# e-wall-smd.net
KiCad netlist of a schematic drawn in EAGLE
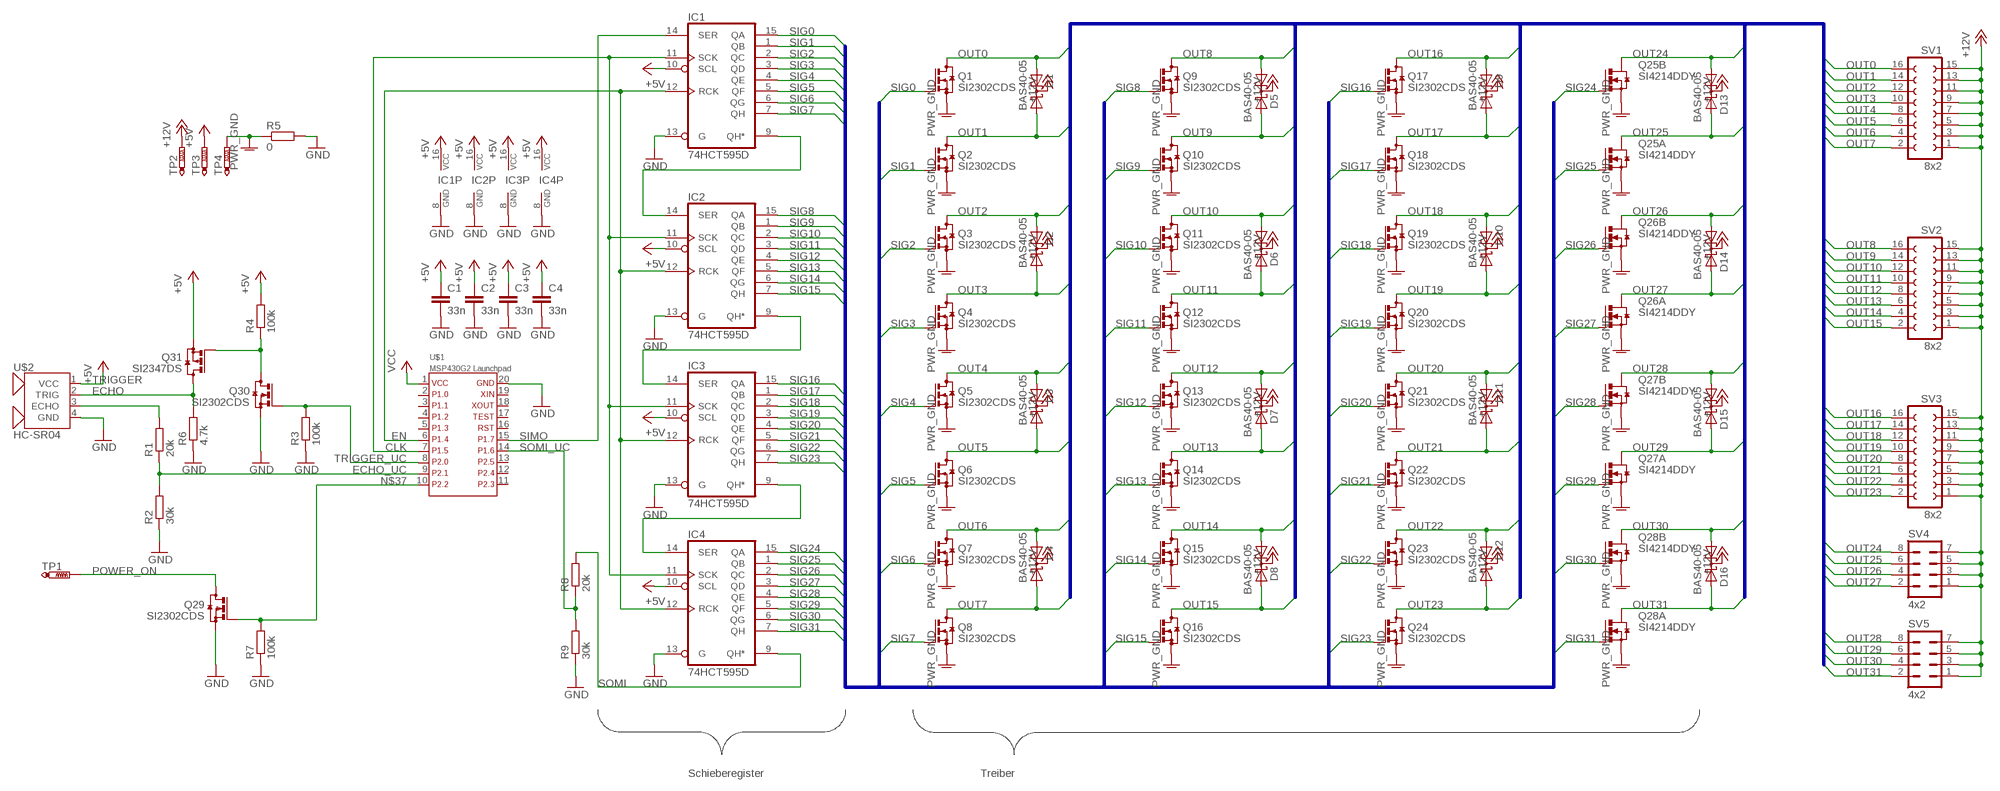
[diagram p0: schematic, sheet 1]

(export (version "E")
  (design (tool "Eeschema 10.0.6"))
  (components
    (comp (ref "C1")
      (value "33n")
      (footprint "eagle-import:C1206")
      (libsource (lib "eagle-import") (part "C-EUC1206"))
    )
    (comp (ref "C2")
      (value "33n")
      (footprint "eagle-import:C1206")
      (libsource (lib "eagle-import") (part "C-EUC1206"))
    )
    (comp (ref "C3")
      (value "33n")
      (footprint "eagle-import:C1206")
      (libsource (lib "eagle-import") (part "C-EUC1206"))
    )
    (comp (ref "C4")
      (value "33n")
      (footprint "eagle-import:C1206")
      (libsource (lib "eagle-import") (part "C-EUC1206"))
    )
    (comp (ref "D1")
      (value "BAS40-05")
      (footprint "eagle-import:SOT23")
      (libsource (lib "eagle-import") (part "BAS40-05"))
    )
    (comp (ref "D2")
      (value "BAS40-05")
      (footprint "eagle-import:SOT23")
      (libsource (lib "eagle-import") (part "BAS40-05"))
    )
    (comp (ref "D3")
      (value "BAS40-05")
      (footprint "eagle-import:SOT23")
      (libsource (lib "eagle-import") (part "BAS40-05"))
    )
    (comp (ref "D4")
      (value "BAS40-05")
      (footprint "eagle-import:SOT23")
      (libsource (lib "eagle-import") (part "BAS40-05"))
    )
    (comp (ref "D5")
      (value "BAS40-05")
      (footprint "eagle-import:SOT23")
      (libsource (lib "eagle-import") (part "BAS40-05"))
    )
    (comp (ref "D6")
      (value "BAS40-05")
      (footprint "eagle-import:SOT23")
      (libsource (lib "eagle-import") (part "BAS40-05"))
    )
    (comp (ref "D7")
      (value "BAS40-05")
      (footprint "eagle-import:SOT23")
      (libsource (lib "eagle-import") (part "BAS40-05"))
    )
    (comp (ref "D8")
      (value "BAS40-05")
      (footprint "eagle-import:SOT23")
      (libsource (lib "eagle-import") (part "BAS40-05"))
    )
    (comp (ref "D9")
      (value "BAS40-05")
      (footprint "eagle-import:SOT23")
      (libsource (lib "eagle-import") (part "BAS40-05"))
    )
    (comp (ref "D10")
      (value "BAS40-05")
      (footprint "eagle-import:SOT23")
      (libsource (lib "eagle-import") (part "BAS40-05"))
    )
    (comp (ref "D11")
      (value "BAS40-05")
      (footprint "eagle-import:SOT23")
      (libsource (lib "eagle-import") (part "BAS40-05"))
    )
    (comp (ref "D12")
      (value "BAS40-05")
      (footprint "eagle-import:SOT23")
      (libsource (lib "eagle-import") (part "BAS40-05"))
    )
    (comp (ref "D13")
      (value "BAS40-05")
      (footprint "eagle-import:SOT23")
      (libsource (lib "eagle-import") (part "BAS40-05"))
    )
    (comp (ref "D14")
      (value "BAS40-05")
      (footprint "eagle-import:SOT23")
      (libsource (lib "eagle-import") (part "BAS40-05"))
    )
    (comp (ref "D15")
      (value "BAS40-05")
      (footprint "eagle-import:SOT23")
      (libsource (lib "eagle-import") (part "BAS40-05"))
    )
    (comp (ref "D16")
      (value "BAS40-05")
      (footprint "eagle-import:SOT23")
      (libsource (lib "eagle-import") (part "BAS40-05"))
    )
    (comp (ref "IC1")
      (value "74HCT595D")
      (footprint "eagle-import:SO16")
      (libsource (lib "eagle-import") (part "74595DHCT"))
    )
    (comp (ref "IC2")
      (value "74HCT595D")
      (footprint "eagle-import:SO16")
      (libsource (lib "eagle-import") (part "74595DHCT"))
    )
    (comp (ref "IC3")
      (value "74HCT595D")
      (footprint "eagle-import:SO16")
      (libsource (lib "eagle-import") (part "74595DHCT"))
    )
    (comp (ref "IC4")
      (value "74HCT595D")
      (footprint "eagle-import:SO16")
      (libsource (lib "eagle-import") (part "74595DHCT"))
    )
    (comp (ref "Q1")
      (value "SI2302CDS")
      (footprint "eagle-import:SOT23")
      (libsource (lib "eagle-import") (part "BSS123"))
    )
    (comp (ref "Q2")
      (value "SI2302CDS")
      (footprint "eagle-import:SOT23")
      (libsource (lib "eagle-import") (part "BSS123"))
    )
    (comp (ref "Q3")
      (value "SI2302CDS")
      (footprint "eagle-import:SOT23")
      (libsource (lib "eagle-import") (part "BSS123"))
    )
    (comp (ref "Q4")
      (value "SI2302CDS")
      (footprint "eagle-import:SOT23")
      (libsource (lib "eagle-import") (part "BSS123"))
    )
    (comp (ref "Q5")
      (value "SI2302CDS")
      (footprint "eagle-import:SOT23")
      (libsource (lib "eagle-import") (part "BSS123"))
    )
    (comp (ref "Q6")
      (value "SI2302CDS")
      (footprint "eagle-import:SOT23")
      (libsource (lib "eagle-import") (part "BSS123"))
    )
    (comp (ref "Q7")
      (value "SI2302CDS")
      (footprint "eagle-import:SOT23")
      (libsource (lib "eagle-import") (part "BSS123"))
    )
    (comp (ref "Q8")
      (value "SI2302CDS")
      (footprint "eagle-import:SOT23")
      (libsource (lib "eagle-import") (part "BSS123"))
    )
    (comp (ref "Q9")
      (value "SI2302CDS")
      (footprint "eagle-import:SOT23")
      (libsource (lib "eagle-import") (part "BSS123"))
    )
    (comp (ref "Q10")
      (value "SI2302CDS")
      (footprint "eagle-import:SOT23")
      (libsource (lib "eagle-import") (part "BSS123"))
    )
    (comp (ref "Q11")
      (value "SI2302CDS")
      (footprint "eagle-import:SOT23")
      (libsource (lib "eagle-import") (part "BSS123"))
    )
    (comp (ref "Q12")
      (value "SI2302CDS")
      (footprint "eagle-import:SOT23")
      (libsource (lib "eagle-import") (part "BSS123"))
    )
    (comp (ref "Q13")
      (value "SI2302CDS")
      (footprint "eagle-import:SOT23")
      (libsource (lib "eagle-import") (part "BSS123"))
    )
    (comp (ref "Q14")
      (value "SI2302CDS")
      (footprint "eagle-import:SOT23")
      (libsource (lib "eagle-import") (part "BSS123"))
    )
    (comp (ref "Q15")
      (value "SI2302CDS")
      (footprint "eagle-import:SOT23")
      (libsource (lib "eagle-import") (part "BSS123"))
    )
    (comp (ref "Q16")
      (value "SI2302CDS")
      (footprint "eagle-import:SOT23")
      (libsource (lib "eagle-import") (part "BSS123"))
    )
    (comp (ref "Q17")
      (value "SI2302CDS")
      (footprint "eagle-import:SOT23")
      (libsource (lib "eagle-import") (part "BSS123"))
    )
    (comp (ref "Q18")
      (value "SI2302CDS")
      (footprint "eagle-import:SOT23")
      (libsource (lib "eagle-import") (part "BSS123"))
    )
    (comp (ref "Q19")
      (value "SI2302CDS")
      (footprint "eagle-import:SOT23")
      (libsource (lib "eagle-import") (part "BSS123"))
    )
    (comp (ref "Q20")
      (value "SI2302CDS")
      (footprint "eagle-import:SOT23")
      (libsource (lib "eagle-import") (part "BSS123"))
    )
    (comp (ref "Q21")
      (value "SI2302CDS")
      (footprint "eagle-import:SOT23")
      (libsource (lib "eagle-import") (part "BSS123"))
    )
    (comp (ref "Q22")
      (value "SI2302CDS")
      (footprint "eagle-import:SOT23")
      (libsource (lib "eagle-import") (part "BSS123"))
    )
    (comp (ref "Q23")
      (value "SI2302CDS")
      (footprint "eagle-import:SOT23")
      (libsource (lib "eagle-import") (part "BSS123"))
    )
    (comp (ref "Q24")
      (value "SI2302CDS")
      (footprint "eagle-import:SOT23")
      (libsource (lib "eagle-import") (part "BSS123"))
    )
    (comp (ref "Q25")
      (value "SI4214DDY")
      (footprint "eagle-import:SO-08")
      (libsource (lib "eagle-import") (part "IRF8313P"))
    )
    (comp (ref "Q26")
      (value "SI4214DDY")
      (footprint "eagle-import:SO-08")
      (libsource (lib "eagle-import") (part "IRF8313P"))
    )
    (comp (ref "Q27")
      (value "SI4214DDY")
      (footprint "eagle-import:SO-08")
      (libsource (lib "eagle-import") (part "IRF8313P"))
    )
    (comp (ref "Q28")
      (value "SI4214DDY")
      (footprint "eagle-import:SO-08")
      (libsource (lib "eagle-import") (part "IRF8313P"))
    )
    (comp (ref "Q29")
      (value "SI2302CDS")
      (footprint "eagle-import:SOT23")
      (libsource (lib "eagle-import") (part "BSS123"))
    )
    (comp (ref "Q30")
      (value "SI2302CDS")
      (footprint "eagle-import:SOT23")
      (libsource (lib "eagle-import") (part "BSS123"))
    )
    (comp (ref "Q31")
      (value "SI2347DS")
      (footprint "eagle-import:SOT23")
      (libsource (lib "eagle-import") (part "BSS84"))
    )
    (comp (ref "R1")
      (value "20k")
      (footprint "eagle-import:R1206")
      (libsource (lib "eagle-import") (part "R-EU_R1206"))
    )
    (comp (ref "R2")
      (value "30k")
      (footprint "eagle-import:R1206")
      (libsource (lib "eagle-import") (part "R-EU_R1206"))
    )
    (comp (ref "R3")
      (value "100k")
      (footprint "eagle-import:R1206")
      (libsource (lib "eagle-import") (part "R-EU_R1206"))
    )
    (comp (ref "R4")
      (value "100k")
      (footprint "eagle-import:R1206")
      (libsource (lib "eagle-import") (part "R-EU_R1206"))
    )
    (comp (ref "R5")
      (value "0")
      (footprint "eagle-import:R1206")
      (libsource (lib "eagle-import") (part "R-EU_R1206"))
    )
    (comp (ref "R6")
      (value "4.7k")
      (footprint "eagle-import:R1206")
      (libsource (lib "eagle-import") (part "R-EU_R1206"))
    )
    (comp (ref "R7")
      (value "100k")
      (footprint "eagle-import:R1206")
      (libsource (lib "eagle-import") (part "R-EU_R1206"))
    )
    (comp (ref "R8")
      (value "20k")
      (footprint "eagle-import:R1206")
      (libsource (lib "eagle-import") (part "R-EU_R1206"))
    )
    (comp (ref "R9")
      (value "30k")
      (footprint "eagle-import:R1206")
      (libsource (lib "eagle-import") (part "R-EU_R1206"))
    )
    (comp (ref "SV1")
      (value "8x2")
      (footprint "eagle-import:FE08-2")
      (libsource (lib "eagle-import") (part "FE08-2"))
    )
    (comp (ref "SV2")
      (value "8x2")
      (footprint "eagle-import:FE08-2")
      (libsource (lib "eagle-import") (part "FE08-2"))
    )
    (comp (ref "SV3")
      (value "8x2")
      (footprint "eagle-import:FE08-2")
      (libsource (lib "eagle-import") (part "FE08-2"))
    )
    (comp (ref "SV4")
      (value "4x2")
      (footprint "eagle-import:MA04-2")
      (libsource (lib "eagle-import") (part "MA04-2"))
    )
    (comp (ref "SV5")
      (value "4x2")
      (footprint "eagle-import:MA04-2")
      (libsource (lib "eagle-import") (part "MA04-2"))
    )
    (comp (ref "TP1")
      (value "PTR1PAD1-20")
      (footprint "eagle-import:P1-20")
      (libsource (lib "eagle-import") (part "PTR1PAD1-20"))
    )
    (comp (ref "TP2")
      (value "PTR1PAD1-20")
      (footprint "eagle-import:P1-20")
      (libsource (lib "eagle-import") (part "PTR1PAD1-20"))
    )
    (comp (ref "TP3")
      (value "PTR1PAD1-20")
      (footprint "eagle-import:P1-20")
      (libsource (lib "eagle-import") (part "PTR1PAD1-20"))
    )
    (comp (ref "TP4")
      (value "PTR1PAD1-20")
      (footprint "eagle-import:P1-20")
      (libsource (lib "eagle-import") (part "PTR1PAD1-20"))
    )
    (comp (ref "U$1")
      (value "MSP430G2 Launchpad")
      (footprint "eagle-import:MSP430LAUNCHPAD_BASIC")
      (libsource (lib "eagle-import") (part "MSP430LAUNCHPAD_BASIC"))
    )
    (comp (ref "U$2")
      (value "HC-SR04")
      (footprint "eagle-import:HC-SR04")
      (libsource (lib "eagle-import") (part "HC-SR04"))
    )
  )
  (nets
    (net (code "1") (name "+5V") (class "Default")
      (node (ref "C1") (pin "1") (pinfunction "1_1") (pintype "passive"))
      (node (ref "C2") (pin "1") (pinfunction "1_1") (pintype "passive"))
      (node (ref "C3") (pin "1") (pinfunction "1_1") (pintype "passive"))
      (node (ref "C4") (pin "1") (pinfunction "1_1") (pintype "passive"))
      (node (ref "IC1") (pin "10") (pinfunction "SCL_10") (pintype "input"))
      (node (ref "IC1") (pin "16") (pinfunction "VCC_16") (pintype "power_in"))
      (node (ref "IC2") (pin "10") (pinfunction "SCL_10") (pintype "input"))
      (node (ref "IC2") (pin "16") (pinfunction "VCC_16") (pintype "power_in"))
      (node (ref "IC3") (pin "10") (pinfunction "SCL_10") (pintype "input"))
      (node (ref "IC3") (pin "16") (pinfunction "VCC_16") (pintype "power_in"))
      (node (ref "IC4") (pin "10") (pinfunction "SCL_10") (pintype "input"))
      (node (ref "IC4") (pin "16") (pinfunction "VCC_16") (pintype "power_in"))
      (node (ref "Q31") (pin "2") (pinfunction "S_2") (pintype "passive"))
      (node (ref "R4") (pin "2") (pinfunction "2_2") (pintype "passive"))
      (node (ref "TP3") (pin "TP") (pinfunction "TP_TP") (pintype "input"))
      (node (ref "U$2") (pin "1") (pinfunction "VCC_1") (pintype "bidirectional"))
    )
    (net (code "2") (name "+12V") (class "Default")
      (node (ref "D1") (pin "3") (pinfunction "C_3") (pintype "passive"))
      (node (ref "D10") (pin "3") (pinfunction "C_3") (pintype "passive"))
      (node (ref "D11") (pin "3") (pinfunction "C_3") (pintype "passive"))
      (node (ref "D12") (pin "3") (pinfunction "C_3") (pintype "passive"))
      (node (ref "D13") (pin "3") (pinfunction "C_3") (pintype "passive"))
      (node (ref "D14") (pin "3") (pinfunction "C_3") (pintype "passive"))
      (node (ref "D15") (pin "3") (pinfunction "C_3") (pintype "passive"))
      (node (ref "D16") (pin "3") (pinfunction "C_3") (pintype "passive"))
      (node (ref "D2") (pin "3") (pinfunction "C_3") (pintype "passive"))
      (node (ref "D3") (pin "3") (pinfunction "C_3") (pintype "passive"))
      (node (ref "D4") (pin "3") (pinfunction "C_3") (pintype "passive"))
      (node (ref "D5") (pin "3") (pinfunction "C_3") (pintype "passive"))
      (node (ref "D6") (pin "3") (pinfunction "C_3") (pintype "passive"))
      (node (ref "D7") (pin "3") (pinfunction "C_3") (pintype "passive"))
      (node (ref "D8") (pin "3") (pinfunction "C_3") (pintype "passive"))
      (node (ref "D9") (pin "3") (pinfunction "C_3") (pintype "passive"))
      (node (ref "SV1") (pin "1") (pinfunction "1_1") (pintype "passive"))
      (node (ref "SV1") (pin "11") (pinfunction "11_11") (pintype "passive"))
      (node (ref "SV1") (pin "13") (pinfunction "13_13") (pintype "passive"))
      (node (ref "SV1") (pin "15") (pinfunction "15_15") (pintype "passive"))
      (node (ref "SV1") (pin "3") (pinfunction "3_3") (pintype "passive"))
      (node (ref "SV1") (pin "5") (pinfunction "5_5") (pintype "passive"))
      (node (ref "SV1") (pin "7") (pinfunction "7_7") (pintype "passive"))
      (node (ref "SV1") (pin "9") (pinfunction "9_9") (pintype "passive"))
      (node (ref "SV2") (pin "1") (pinfunction "1_1") (pintype "passive"))
      (node (ref "SV2") (pin "11") (pinfunction "11_11") (pintype "passive"))
      (node (ref "SV2") (pin "13") (pinfunction "13_13") (pintype "passive"))
      (node (ref "SV2") (pin "15") (pinfunction "15_15") (pintype "passive"))
      (node (ref "SV2") (pin "3") (pinfunction "3_3") (pintype "passive"))
      (node (ref "SV2") (pin "5") (pinfunction "5_5") (pintype "passive"))
      (node (ref "SV2") (pin "7") (pinfunction "7_7") (pintype "passive"))
      (node (ref "SV2") (pin "9") (pinfunction "9_9") (pintype "passive"))
      (node (ref "SV3") (pin "1") (pinfunction "1_1") (pintype "passive"))
      (node (ref "SV3") (pin "11") (pinfunction "11_11") (pintype "passive"))
      (node (ref "SV3") (pin "13") (pinfunction "13_13") (pintype "passive"))
      (node (ref "SV3") (pin "15") (pinfunction "15_15") (pintype "passive"))
      (node (ref "SV3") (pin "3") (pinfunction "3_3") (pintype "passive"))
      (node (ref "SV3") (pin "5") (pinfunction "5_5") (pintype "passive"))
      (node (ref "SV3") (pin "7") (pinfunction "7_7") (pintype "passive"))
      (node (ref "SV3") (pin "9") (pinfunction "9_9") (pintype "passive"))
      (node (ref "SV4") (pin "1") (pinfunction "1_1") (pintype "passive"))
      (node (ref "SV4") (pin "3") (pinfunction "3_3") (pintype "passive"))
      (node (ref "SV4") (pin "5") (pinfunction "5_5") (pintype "passive"))
      (node (ref "SV4") (pin "7") (pinfunction "7_7") (pintype "passive"))
      (node (ref "SV5") (pin "1") (pinfunction "1_1") (pintype "passive"))
      (node (ref "SV5") (pin "3") (pinfunction "3_3") (pintype "passive"))
      (node (ref "SV5") (pin "5") (pinfunction "5_5") (pintype "passive"))
      (node (ref "SV5") (pin "7") (pinfunction "7_7") (pintype "passive"))
      (node (ref "TP2") (pin "TP") (pinfunction "TP_TP") (pintype "input"))
    )
    (net (code "3") (name "/CLK") (class "Default")
      (node (ref "IC1") (pin "11") (pinfunction "SCK_11") (pintype "input"))
      (node (ref "IC2") (pin "11") (pinfunction "SCK_11") (pintype "input"))
      (node (ref "IC3") (pin "11") (pinfunction "SCK_11") (pintype "input"))
      (node (ref "IC4") (pin "11") (pinfunction "SCK_11") (pintype "input"))
      (node (ref "U$1") (pin "7") (pinfunction "7_7") (pintype "bidirectional"))
    )
    (net (code "4") (name "/ECHO") (class "Default")
      (node (ref "R1") (pin "2") (pinfunction "2_2") (pintype "passive"))
      (node (ref "U$2") (pin "3") (pinfunction "ECHO_3") (pintype "bidirectional"))
    )
    (net (code "5") (name "/ECHO_UC") (class "Default")
      (node (ref "R1") (pin "1") (pinfunction "1_1") (pintype "passive"))
      (node (ref "R2") (pin "2") (pinfunction "2_2") (pintype "passive"))
      (node (ref "U$1") (pin "9") (pinfunction "9_9") (pintype "bidirectional"))
    )
    (net (code "6") (name "/EN") (class "Default")
      (node (ref "IC1") (pin "12") (pinfunction "RCK_12") (pintype "input"))
      (node (ref "IC2") (pin "12") (pinfunction "RCK_12") (pintype "input"))
      (node (ref "IC3") (pin "12") (pinfunction "RCK_12") (pintype "input"))
      (node (ref "IC4") (pin "12") (pinfunction "RCK_12") (pintype "input"))
      (node (ref "U$1") (pin "6") (pinfunction "6_6") (pintype "bidirectional"))
    )
    (net (code "7") (name "/N$37") (class "Default")
      (node (ref "Q29") (pin "1") (pinfunction "G_1") (pintype "passive"))
      (node (ref "R7") (pin "2") (pinfunction "2_2") (pintype "passive"))
      (node (ref "U$1") (pin "10") (pinfunction "10_10") (pintype "bidirectional"))
    )
    (net (code "8") (name "/OUT0") (class "Default")
      (node (ref "D1") (pin "2") (pinfunction "A2_2") (pintype "passive"))
      (node (ref "Q1") (pin "3") (pinfunction "D_3") (pintype "passive"))
      (node (ref "SV1") (pin "16") (pinfunction "16_16") (pintype "passive"))
    )
    (net (code "9") (name "/OUT1") (class "Default")
      (node (ref "D1") (pin "1") (pinfunction "A1_1") (pintype "passive"))
      (node (ref "Q2") (pin "3") (pinfunction "D_3") (pintype "passive"))
      (node (ref "SV1") (pin "14") (pinfunction "14_14") (pintype "passive"))
    )
    (net (code "10") (name "/OUT2") (class "Default")
      (node (ref "D2") (pin "2") (pinfunction "A2_2") (pintype "passive"))
      (node (ref "Q3") (pin "3") (pinfunction "D_3") (pintype "passive"))
      (node (ref "SV1") (pin "12") (pinfunction "12_12") (pintype "passive"))
    )
    (net (code "11") (name "/OUT3") (class "Default")
      (node (ref "D2") (pin "1") (pinfunction "A1_1") (pintype "passive"))
      (node (ref "Q4") (pin "3") (pinfunction "D_3") (pintype "passive"))
      (node (ref "SV1") (pin "10") (pinfunction "10_10") (pintype "passive"))
    )
    (net (code "12") (name "/OUT4") (class "Default")
      (node (ref "D3") (pin "2") (pinfunction "A2_2") (pintype "passive"))
      (node (ref "Q5") (pin "3") (pinfunction "D_3") (pintype "passive"))
      (node (ref "SV1") (pin "8") (pinfunction "8_8") (pintype "passive"))
    )
    (net (code "13") (name "/OUT5") (class "Default")
      (node (ref "D3") (pin "1") (pinfunction "A1_1") (pintype "passive"))
      (node (ref "Q6") (pin "3") (pinfunction "D_3") (pintype "passive"))
      (node (ref "SV1") (pin "6") (pinfunction "6_6") (pintype "passive"))
    )
    (net (code "14") (name "/OUT6") (class "Default")
      (node (ref "D4") (pin "2") (pinfunction "A2_2") (pintype "passive"))
      (node (ref "Q7") (pin "3") (pinfunction "D_3") (pintype "passive"))
      (node (ref "SV1") (pin "4") (pinfunction "4_4") (pintype "passive"))
    )
    (net (code "15") (name "/OUT7") (class "Default")
      (node (ref "D4") (pin "1") (pinfunction "A1_1") (pintype "passive"))
      (node (ref "Q8") (pin "3") (pinfunction "D_3") (pintype "passive"))
      (node (ref "SV1") (pin "2") (pinfunction "2_2") (pintype "passive"))
    )
    (net (code "16") (name "/OUT8") (class "Default")
      (node (ref "D5") (pin "1") (pinfunction "A1_1") (pintype "passive"))
      (node (ref "Q9") (pin "3") (pinfunction "D_3") (pintype "passive"))
      (node (ref "SV2") (pin "16") (pinfunction "16_16") (pintype "passive"))
    )
    (net (code "17") (name "/OUT9") (class "Default")
      (node (ref "D5") (pin "2") (pinfunction "A2_2") (pintype "passive"))
      (node (ref "Q10") (pin "3") (pinfunction "D_3") (pintype "passive"))
      (node (ref "SV2") (pin "14") (pinfunction "14_14") (pintype "passive"))
    )
    (net (code "18") (name "/OUT10") (class "Default")
      (node (ref "D6") (pin "1") (pinfunction "A1_1") (pintype "passive"))
      (node (ref "Q11") (pin "3") (pinfunction "D_3") (pintype "passive"))
      (node (ref "SV2") (pin "12") (pinfunction "12_12") (pintype "passive"))
    )
    (net (code "19") (name "/OUT11") (class "Default")
      (node (ref "D6") (pin "2") (pinfunction "A2_2") (pintype "passive"))
      (node (ref "Q12") (pin "3") (pinfunction "D_3") (pintype "passive"))
      (node (ref "SV2") (pin "10") (pinfunction "10_10") (pintype "passive"))
    )
    (net (code "20") (name "/OUT12") (class "Default")
      (node (ref "D7") (pin "1") (pinfunction "A1_1") (pintype "passive"))
      (node (ref "Q13") (pin "3") (pinfunction "D_3") (pintype "passive"))
      (node (ref "SV2") (pin "8") (pinfunction "8_8") (pintype "passive"))
    )
    (net (code "21") (name "/OUT13") (class "Default")
      (node (ref "D7") (pin "2") (pinfunction "A2_2") (pintype "passive"))
      (node (ref "Q14") (pin "3") (pinfunction "D_3") (pintype "passive"))
      (node (ref "SV2") (pin "6") (pinfunction "6_6") (pintype "passive"))
    )
    (net (code "22") (name "/OUT14") (class "Default")
      (node (ref "D8") (pin "1") (pinfunction "A1_1") (pintype "passive"))
      (node (ref "Q15") (pin "3") (pinfunction "D_3") (pintype "passive"))
      (node (ref "SV2") (pin "4") (pinfunction "4_4") (pintype "passive"))
    )
    (net (code "23") (name "/OUT15") (class "Default")
      (node (ref "D8") (pin "2") (pinfunction "A2_2") (pintype "passive"))
      (node (ref "Q16") (pin "3") (pinfunction "D_3") (pintype "passive"))
      (node (ref "SV2") (pin "2") (pinfunction "2_2") (pintype "passive"))
    )
    (net (code "24") (name "/OUT16") (class "Default")
      (node (ref "D9") (pin "2") (pinfunction "A2_2") (pintype "passive"))
      (node (ref "Q17") (pin "3") (pinfunction "D_3") (pintype "passive"))
      (node (ref "SV3") (pin "16") (pinfunction "16_16") (pintype "passive"))
    )
    (net (code "25") (name "/OUT17") (class "Default")
      (node (ref "D9") (pin "1") (pinfunction "A1_1") (pintype "passive"))
      (node (ref "Q18") (pin "3") (pinfunction "D_3") (pintype "passive"))
      (node (ref "SV3") (pin "14") (pinfunction "14_14") (pintype "passive"))
    )
    (net (code "26") (name "/OUT18") (class "Default")
      (node (ref "D10") (pin "2") (pinfunction "A2_2") (pintype "passive"))
      (node (ref "Q19") (pin "3") (pinfunction "D_3") (pintype "passive"))
      (node (ref "SV3") (pin "12") (pinfunction "12_12") (pintype "passive"))
    )
    (net (code "27") (name "/OUT19") (class "Default")
      (node (ref "D10") (pin "1") (pinfunction "A1_1") (pintype "passive"))
      (node (ref "Q20") (pin "3") (pinfunction "D_3") (pintype "passive"))
      (node (ref "SV3") (pin "10") (pinfunction "10_10") (pintype "passive"))
    )
    (net (code "28") (name "/OUT20") (class "Default")
      (node (ref "D11") (pin "2") (pinfunction "A2_2") (pintype "passive"))
      (node (ref "Q21") (pin "3") (pinfunction "D_3") (pintype "passive"))
      (node (ref "SV3") (pin "8") (pinfunction "8_8") (pintype "passive"))
    )
    (net (code "29") (name "/OUT21") (class "Default")
      (node (ref "D11") (pin "1") (pinfunction "A1_1") (pintype "passive"))
      (node (ref "Q22") (pin "3") (pinfunction "D_3") (pintype "passive"))
      (node (ref "SV3") (pin "6") (pinfunction "6_6") (pintype "passive"))
    )
    (net (code "30") (name "/OUT22") (class "Default")
      (node (ref "D12") (pin "2") (pinfunction "A2_2") (pintype "passive"))
      (node (ref "Q23") (pin "3") (pinfunction "D_3") (pintype "passive"))
      (node (ref "SV3") (pin "4") (pinfunction "4_4") (pintype "passive"))
    )
    (net (code "31") (name "/OUT23") (class "Default")
      (node (ref "D12") (pin "1") (pinfunction "A1_1") (pintype "passive"))
      (node (ref "Q24") (pin "3") (pinfunction "D_3") (pintype "passive"))
      (node (ref "SV3") (pin "2") (pinfunction "2_2") (pintype "passive"))
    )
    (net (code "32") (name "/OUT24") (class "Default")
      (node (ref "D13") (pin "1") (pinfunction "A1_1") (pintype "passive"))
      (node (ref "Q25") (pin "7") (pinfunction "D_7") (pintype "passive"))
      (node (ref "Q25") (pin "8") (pinfunction "D_8") (pintype "passive"))
      (node (ref "SV4") (pin "8") (pinfunction "8_8") (pintype "passive"))
    )
    (net (code "33") (name "/OUT25") (class "Default")
      (node (ref "D13") (pin "2") (pinfunction "A2_2") (pintype "passive"))
      (node (ref "Q25") (pin "5") (pinfunction "D_5") (pintype "passive"))
      (node (ref "Q25") (pin "6") (pinfunction "D_6") (pintype "passive"))
      (node (ref "SV4") (pin "6") (pinfunction "6_6") (pintype "passive"))
    )
    (net (code "34") (name "/OUT26") (class "Default")
      (node (ref "D14") (pin "1") (pinfunction "A1_1") (pintype "passive"))
      (node (ref "Q26") (pin "7") (pinfunction "D_7") (pintype "passive"))
      (node (ref "Q26") (pin "8") (pinfunction "D_8") (pintype "passive"))
      (node (ref "SV4") (pin "4") (pinfunction "4_4") (pintype "passive"))
    )
    (net (code "35") (name "/OUT27") (class "Default")
      (node (ref "D14") (pin "2") (pinfunction "A2_2") (pintype "passive"))
      (node (ref "Q26") (pin "5") (pinfunction "D_5") (pintype "passive"))
      (node (ref "Q26") (pin "6") (pinfunction "D_6") (pintype "passive"))
      (node (ref "SV4") (pin "2") (pinfunction "2_2") (pintype "passive"))
    )
    (net (code "36") (name "/OUT28") (class "Default")
      (node (ref "D15") (pin "1") (pinfunction "A1_1") (pintype "passive"))
      (node (ref "Q27") (pin "7") (pinfunction "D_7") (pintype "passive"))
      (node (ref "Q27") (pin "8") (pinfunction "D_8") (pintype "passive"))
      (node (ref "SV5") (pin "8") (pinfunction "8_8") (pintype "passive"))
    )
    (net (code "37") (name "/OUT29") (class "Default")
      (node (ref "D15") (pin "2") (pinfunction "A2_2") (pintype "passive"))
      (node (ref "Q27") (pin "5") (pinfunction "D_5") (pintype "passive"))
      (node (ref "Q27") (pin "6") (pinfunction "D_6") (pintype "passive"))
      (node (ref "SV5") (pin "6") (pinfunction "6_6") (pintype "passive"))
    )
    (net (code "38") (name "/OUT30") (class "Default")
      (node (ref "D16") (pin "1") (pinfunction "A1_1") (pintype "passive"))
      (node (ref "Q28") (pin "7") (pinfunction "D_7") (pintype "passive"))
      (node (ref "Q28") (pin "8") (pinfunction "D_8") (pintype "passive"))
      (node (ref "SV5") (pin "4") (pinfunction "4_4") (pintype "passive"))
    )
    (net (code "39") (name "/OUT31") (class "Default")
      (node (ref "D16") (pin "2") (pinfunction "A2_2") (pintype "passive"))
      (node (ref "Q28") (pin "5") (pinfunction "D_5") (pintype "passive"))
      (node (ref "Q28") (pin "6") (pinfunction "D_6") (pintype "passive"))
      (node (ref "SV5") (pin "2") (pinfunction "2_2") (pintype "passive"))
    )
    (net (code "40") (name "/POWER_ON") (class "Default")
      (node (ref "Q29") (pin "3") (pinfunction "D_3") (pintype "passive"))
      (node (ref "TP1") (pin "TP") (pinfunction "TP_TP") (pintype "input"))
    )
    (net (code "41") (name "/SIG0") (class "Default")
      (node (ref "IC1") (pin "15") (pinfunction "QA_15") (pintype "tri_state"))
      (node (ref "Q1") (pin "1") (pinfunction "G_1") (pintype "passive"))
    )
    (net (code "42") (name "/SIG1") (class "Default")
      (node (ref "IC1") (pin "1") (pinfunction "QB_1") (pintype "tri_state"))
      (node (ref "Q2") (pin "1") (pinfunction "G_1") (pintype "passive"))
    )
    (net (code "43") (name "/SIG2") (class "Default")
      (node (ref "IC1") (pin "2") (pinfunction "QC_2") (pintype "tri_state"))
      (node (ref "Q3") (pin "1") (pinfunction "G_1") (pintype "passive"))
    )
    (net (code "44") (name "/SIG3") (class "Default")
      (node (ref "IC1") (pin "3") (pinfunction "QD_3") (pintype "tri_state"))
      (node (ref "Q4") (pin "1") (pinfunction "G_1") (pintype "passive"))
    )
    (net (code "45") (name "/SIG4") (class "Default")
      (node (ref "IC1") (pin "4") (pinfunction "QE_4") (pintype "tri_state"))
      (node (ref "Q5") (pin "1") (pinfunction "G_1") (pintype "passive"))
    )
    (net (code "46") (name "/SIG5") (class "Default")
      (node (ref "IC1") (pin "5") (pinfunction "QF_5") (pintype "tri_state"))
      (node (ref "Q6") (pin "1") (pinfunction "G_1") (pintype "passive"))
    )
    (net (code "47") (name "/SIG6") (class "Default")
      (node (ref "IC1") (pin "6") (pinfunction "QG_6") (pintype "tri_state"))
      (node (ref "Q7") (pin "1") (pinfunction "G_1") (pintype "passive"))
    )
    (net (code "48") (name "/SIG7") (class "Default")
      (node (ref "IC1") (pin "7") (pinfunction "QH_7") (pintype "tri_state"))
      (node (ref "Q8") (pin "1") (pinfunction "G_1") (pintype "passive"))
    )
    (net (code "49") (name "/SIG8") (class "Default")
      (node (ref "IC2") (pin "15") (pinfunction "QA_15") (pintype "tri_state"))
      (node (ref "Q9") (pin "1") (pinfunction "G_1") (pintype "passive"))
    )
    (net (code "50") (name "/SIG9") (class "Default")
      (node (ref "IC2") (pin "1") (pinfunction "QB_1") (pintype "tri_state"))
      (node (ref "Q10") (pin "1") (pinfunction "G_1") (pintype "passive"))
    )
    (net (code "51") (name "/SIG10") (class "Default")
      (node (ref "IC2") (pin "2") (pinfunction "QC_2") (pintype "tri_state"))
      (node (ref "Q11") (pin "1") (pinfunction "G_1") (pintype "passive"))
    )
    (net (code "52") (name "/SIG11") (class "Default")
      (node (ref "IC2") (pin "3") (pinfunction "QD_3") (pintype "tri_state"))
      (node (ref "Q12") (pin "1") (pinfunction "G_1") (pintype "passive"))
    )
    (net (code "53") (name "/SIG12") (class "Default")
      (node (ref "IC2") (pin "4") (pinfunction "QE_4") (pintype "tri_state"))
      (node (ref "Q13") (pin "1") (pinfunction "G_1") (pintype "passive"))
    )
    (net (code "54") (name "/SIG13") (class "Default")
      (node (ref "IC2") (pin "5") (pinfunction "QF_5") (pintype "tri_state"))
      (node (ref "Q14") (pin "1") (pinfunction "G_1") (pintype "passive"))
    )
    (net (code "55") (name "/SIG14") (class "Default")
      (node (ref "IC2") (pin "6") (pinfunction "QG_6") (pintype "tri_state"))
      (node (ref "Q15") (pin "1") (pinfunction "G_1") (pintype "passive"))
    )
    (net (code "56") (name "/SIG15") (class "Default")
      (node (ref "IC2") (pin "7") (pinfunction "QH_7") (pintype "tri_state"))
      (node (ref "Q16") (pin "1") (pinfunction "G_1") (pintype "passive"))
    )
    (net (code "57") (name "/SIG16") (class "Default")
      (node (ref "IC3") (pin "15") (pinfunction "QA_15") (pintype "tri_state"))
      (node (ref "Q17") (pin "1") (pinfunction "G_1") (pintype "passive"))
    )
    (net (code "58") (name "/SIG17") (class "Default")
      (node (ref "IC3") (pin "1") (pinfunction "QB_1") (pintype "tri_state"))
      (node (ref "Q18") (pin "1") (pinfunction "G_1") (pintype "passive"))
    )
    (net (code "59") (name "/SIG18") (class "Default")
      (node (ref "IC3") (pin "2") (pinfunction "QC_2") (pintype "tri_state"))
      (node (ref "Q19") (pin "1") (pinfunction "G_1") (pintype "passive"))
    )
    (net (code "60") (name "/SIG19") (class "Default")
      (node (ref "IC3") (pin "3") (pinfunction "QD_3") (pintype "tri_state"))
      (node (ref "Q20") (pin "1") (pinfunction "G_1") (pintype "passive"))
    )
    (net (code "61") (name "/SIG20") (class "Default")
      (node (ref "IC3") (pin "4") (pinfunction "QE_4") (pintype "tri_state"))
      (node (ref "Q21") (pin "1") (pinfunction "G_1") (pintype "passive"))
    )
    (net (code "62") (name "/SIG21") (class "Default")
      (node (ref "IC3") (pin "5") (pinfunction "QF_5") (pintype "tri_state"))
      (node (ref "Q22") (pin "1") (pinfunction "G_1") (pintype "passive"))
    )
    (net (code "63") (name "/SIG22") (class "Default")
      (node (ref "IC3") (pin "6") (pinfunction "QG_6") (pintype "tri_state"))
      (node (ref "Q23") (pin "1") (pinfunction "G_1") (pintype "passive"))
    )
    (net (code "64") (name "/SIG23") (class "Default")
      (node (ref "IC3") (pin "7") (pinfunction "QH_7") (pintype "tri_state"))
      (node (ref "Q24") (pin "1") (pinfunction "G_1") (pintype "passive"))
    )
    (net (code "65") (name "/SIG24") (class "Default")
      (node (ref "IC4") (pin "15") (pinfunction "QA_15") (pintype "tri_state"))
      (node (ref "Q25") (pin "2") (pinfunction "G_2") (pintype "passive"))
    )
    (net (code "66") (name "/SIG25") (class "Default")
      (node (ref "IC4") (pin "1") (pinfunction "QB_1") (pintype "tri_state"))
      (node (ref "Q25") (pin "4") (pinfunction "G_4") (pintype "passive"))
    )
    (net (code "67") (name "/SIG26") (class "Default")
      (node (ref "IC4") (pin "2") (pinfunction "QC_2") (pintype "tri_state"))
      (node (ref "Q26") (pin "2") (pinfunction "G_2") (pintype "passive"))
    )
    (net (code "68") (name "/SIG27") (class "Default")
      (node (ref "IC4") (pin "3") (pinfunction "QD_3") (pintype "tri_state"))
      (node (ref "Q26") (pin "4") (pinfunction "G_4") (pintype "passive"))
    )
    (net (code "69") (name "/SIG28") (class "Default")
      (node (ref "IC4") (pin "4") (pinfunction "QE_4") (pintype "tri_state"))
      (node (ref "Q27") (pin "2") (pinfunction "G_2") (pintype "passive"))
    )
    (net (code "70") (name "/SIG29") (class "Default")
      (node (ref "IC4") (pin "5") (pinfunction "QF_5") (pintype "tri_state"))
      (node (ref "Q27") (pin "4") (pinfunction "G_4") (pintype "passive"))
    )
    (net (code "71") (name "/SIG30") (class "Default")
      (node (ref "IC4") (pin "6") (pinfunction "QG_6") (pintype "tri_state"))
      (node (ref "Q28") (pin "2") (pinfunction "G_2") (pintype "passive"))
    )
    (net (code "72") (name "/SIG31") (class "Default")
      (node (ref "IC4") (pin "7") (pinfunction "QH_7") (pintype "tri_state"))
      (node (ref "Q28") (pin "4") (pinfunction "G_4") (pintype "passive"))
    )
    (net (code "73") (name "/SIMO") (class "Default")
      (node (ref "IC1") (pin "14") (pinfunction "SER_14") (pintype "input"))
      (node (ref "U$1") (pin "15") (pinfunction "15_15") (pintype "bidirectional"))
    )
    (net (code "74") (name "/SOMI") (class "Default")
      (node (ref "IC4") (pin "9") (pinfunction "QH*_9") (pintype "tri_state"))
      (node (ref "R8") (pin "2") (pinfunction "2_2") (pintype "passive"))
    )
    (net (code "75") (name "/SOMI_UC") (class "Default")
      (node (ref "R8") (pin "1") (pinfunction "1_1") (pintype "passive"))
      (node (ref "R9") (pin "2") (pinfunction "2_2") (pintype "passive"))
      (node (ref "U$1") (pin "14") (pinfunction "14_14") (pintype "bidirectional"))
    )
    (net (code "76") (name "/TRIGGER") (class "Default")
      (node (ref "Q31") (pin "3") (pinfunction "D_3") (pintype "passive"))
      (node (ref "R6") (pin "2") (pinfunction "2_2") (pintype "passive"))
      (node (ref "U$2") (pin "2") (pinfunction "TRIG_2") (pintype "bidirectional"))
    )
    (net (code "77") (name "/TRIGGER_UC") (class "Default")
      (node (ref "Q30") (pin "1") (pinfunction "G_1") (pintype "passive"))
      (node (ref "R3") (pin "2") (pinfunction "2_2") (pintype "passive"))
      (node (ref "U$1") (pin "8") (pinfunction "8_8") (pintype "bidirectional"))
    )
    (net (code "78") (name "GND") (class "Default")
      (node (ref "C1") (pin "2") (pinfunction "2_2") (pintype "passive"))
      (node (ref "C2") (pin "2") (pinfunction "2_2") (pintype "passive"))
      (node (ref "C3") (pin "2") (pinfunction "2_2") (pintype "passive"))
      (node (ref "C4") (pin "2") (pinfunction "2_2") (pintype "passive"))
      (node (ref "IC1") (pin "13") (pinfunction "G_13") (pintype "input"))
      (node (ref "IC1") (pin "8") (pinfunction "GND_8") (pintype "power_in"))
      (node (ref "IC2") (pin "13") (pinfunction "G_13") (pintype "input"))
      (node (ref "IC2") (pin "8") (pinfunction "GND_8") (pintype "power_in"))
      (node (ref "IC3") (pin "13") (pinfunction "G_13") (pintype "input"))
      (node (ref "IC3") (pin "8") (pinfunction "GND_8") (pintype "power_in"))
      (node (ref "IC4") (pin "13") (pinfunction "G_13") (pintype "input"))
      (node (ref "IC4") (pin "8") (pinfunction "GND_8") (pintype "power_in"))
      (node (ref "Q29") (pin "2") (pinfunction "S_2") (pintype "passive"))
      (node (ref "Q30") (pin "2") (pinfunction "S_2") (pintype "passive"))
      (node (ref "R2") (pin "1") (pinfunction "1_1") (pintype "passive"))
      (node (ref "R3") (pin "1") (pinfunction "1_1") (pintype "passive"))
      (node (ref "R5") (pin "2") (pinfunction "2_2") (pintype "passive"))
      (node (ref "R6") (pin "1") (pinfunction "1_1") (pintype "passive"))
      (node (ref "R7") (pin "1") (pinfunction "1_1") (pintype "passive"))
      (node (ref "R9") (pin "1") (pinfunction "1_1") (pintype "passive"))
      (node (ref "U$1") (pin "20") (pinfunction "20_20") (pintype "bidirectional"))
      (node (ref "U$2") (pin "4") (pinfunction "GND_4") (pintype "bidirectional"))
    )
    (net (code "79") (name "Net-(IC1A-QH*)") (class "Default")
      (node (ref "IC1") (pin "9") (pinfunction "QH*_9") (pintype "tri_state"))
      (node (ref "IC2") (pin "14") (pinfunction "SER_14") (pintype "input"))
    )
    (net (code "80") (name "Net-(IC2A-QH*)") (class "Default")
      (node (ref "IC2") (pin "9") (pinfunction "QH*_9") (pintype "tri_state"))
      (node (ref "IC3") (pin "14") (pinfunction "SER_14") (pintype "input"))
    )
    (net (code "81") (name "Net-(IC3A-QH*)") (class "Default")
      (node (ref "IC3") (pin "9") (pinfunction "QH*_9") (pintype "tri_state"))
      (node (ref "IC4") (pin "14") (pinfunction "SER_14") (pintype "input"))
    )
    (net (code "82") (name "Net-(Q30-D)") (class "Default")
      (node (ref "Q30") (pin "3") (pinfunction "D_3") (pintype "passive"))
      (node (ref "Q31") (pin "1") (pinfunction "G_1") (pintype "passive"))
      (node (ref "R4") (pin "1") (pinfunction "1_1") (pintype "passive"))
    )
    (net (code "83") (name "PWR_GND") (class "Default")
      (node (ref "Q1") (pin "2") (pinfunction "S_2") (pintype "passive"))
      (node (ref "Q10") (pin "2") (pinfunction "S_2") (pintype "passive"))
      (node (ref "Q11") (pin "2") (pinfunction "S_2") (pintype "passive"))
      (node (ref "Q12") (pin "2") (pinfunction "S_2") (pintype "passive"))
      (node (ref "Q13") (pin "2") (pinfunction "S_2") (pintype "passive"))
      (node (ref "Q14") (pin "2") (pinfunction "S_2") (pintype "passive"))
      (node (ref "Q15") (pin "2") (pinfunction "S_2") (pintype "passive"))
      (node (ref "Q16") (pin "2") (pinfunction "S_2") (pintype "passive"))
      (node (ref "Q17") (pin "2") (pinfunction "S_2") (pintype "passive"))
      (node (ref "Q18") (pin "2") (pinfunction "S_2") (pintype "passive"))
      (node (ref "Q19") (pin "2") (pinfunction "S_2") (pintype "passive"))
      (node (ref "Q2") (pin "2") (pinfunction "S_2") (pintype "passive"))
      (node (ref "Q20") (pin "2") (pinfunction "S_2") (pintype "passive"))
      (node (ref "Q21") (pin "2") (pinfunction "S_2") (pintype "passive"))
      (node (ref "Q22") (pin "2") (pinfunction "S_2") (pintype "passive"))
      (node (ref "Q23") (pin "2") (pinfunction "S_2") (pintype "passive"))
      (node (ref "Q24") (pin "2") (pinfunction "S_2") (pintype "passive"))
      (node (ref "Q25") (pin "1") (pinfunction "S_1") (pintype "passive"))
      (node (ref "Q25") (pin "3") (pinfunction "S_3") (pintype "passive"))
      (node (ref "Q26") (pin "1") (pinfunction "S_1") (pintype "passive"))
      (node (ref "Q26") (pin "3") (pinfunction "S_3") (pintype "passive"))
      (node (ref "Q27") (pin "1") (pinfunction "S_1") (pintype "passive"))
      (node (ref "Q27") (pin "3") (pinfunction "S_3") (pintype "passive"))
      (node (ref "Q28") (pin "1") (pinfunction "S_1") (pintype "passive"))
      (node (ref "Q28") (pin "3") (pinfunction "S_3") (pintype "passive"))
      (node (ref "Q3") (pin "2") (pinfunction "S_2") (pintype "passive"))
      (node (ref "Q4") (pin "2") (pinfunction "S_2") (pintype "passive"))
      (node (ref "Q5") (pin "2") (pinfunction "S_2") (pintype "passive"))
      (node (ref "Q6") (pin "2") (pinfunction "S_2") (pintype "passive"))
      (node (ref "Q7") (pin "2") (pinfunction "S_2") (pintype "passive"))
      (node (ref "Q8") (pin "2") (pinfunction "S_2") (pintype "passive"))
      (node (ref "Q9") (pin "2") (pinfunction "S_2") (pintype "passive"))
      (node (ref "R5") (pin "1") (pinfunction "1_1") (pintype "passive"))
      (node (ref "TP4") (pin "TP") (pinfunction "TP_TP") (pintype "input"))
    )
    (net (code "84") (name "VCC") (class "Default")
      (node (ref "U$1") (pin "1") (pinfunction "1_1") (pintype "bidirectional"))
    )
    (net (code "85") (name "unconnected-(U$1-Pad2)") (class "Default")
      (node (ref "U$1") (pin "2") (pinfunction "2_2") (pintype "bidirectional"))
    )
    (net (code "86") (name "unconnected-(U$1-Pad3)") (class "Default")
      (node (ref "U$1") (pin "3") (pinfunction "3_3") (pintype "bidirectional"))
    )
    (net (code "87") (name "unconnected-(U$1-Pad4)") (class "Default")
      (node (ref "U$1") (pin "4") (pinfunction "4_4") (pintype "bidirectional"))
    )
    (net (code "88") (name "unconnected-(U$1-Pad5)") (class "Default")
      (node (ref "U$1") (pin "5") (pinfunction "5_5") (pintype "bidirectional"))
    )
    (net (code "89") (name "unconnected-(U$1-Pad11)") (class "Default")
      (node (ref "U$1") (pin "11") (pinfunction "11_11") (pintype "bidirectional"))
    )
    (net (code "90") (name "unconnected-(U$1-Pad12)") (class "Default")
      (node (ref "U$1") (pin "12") (pinfunction "12_12") (pintype "bidirectional"))
    )
    (net (code "91") (name "unconnected-(U$1-Pad13)") (class "Default")
      (node (ref "U$1") (pin "13") (pinfunction "13_13") (pintype "bidirectional"))
    )
    (net (code "92") (name "unconnected-(U$1-Pad16)") (class "Default")
      (node (ref "U$1") (pin "16") (pinfunction "16_16") (pintype "bidirectional"))
    )
    (net (code "93") (name "unconnected-(U$1-Pad17)") (class "Default")
      (node (ref "U$1") (pin "17") (pinfunction "17_17") (pintype "bidirectional"))
    )
    (net (code "94") (name "unconnected-(U$1-Pad18)") (class "Default")
      (node (ref "U$1") (pin "18") (pinfunction "18_18") (pintype "bidirectional"))
    )
    (net (code "95") (name "unconnected-(U$1-Pad19)") (class "Default")
      (node (ref "U$1") (pin "19") (pinfunction "19_19") (pintype "bidirectional"))
    )
  )
)
